# RaspberryShield.net
KiCad netlist of a schematic drawn in EAGLE
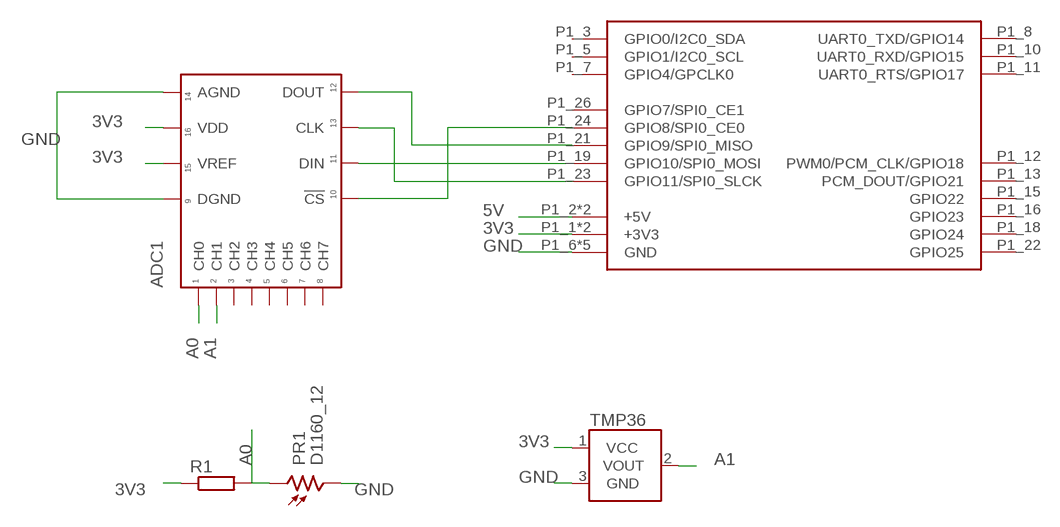
[diagram p0: schematic, sheet 1]

(export (version "E")
  (design (tool "Eeschema 10.0.6"))
  (components
    (comp (ref "ADC1")
      (value "21298EDIP")
      (footprint "eagle-import:DIP16")
      (libsource (lib "eagle-import") (part "21298EDIP"))
    )
    (comp (ref "PR1")
      (value "D1160_12")
      (footprint "eagle-import:D11XX")
      (libsource (lib "eagle-import") (part "D1160_12"))
    )
    (comp (ref "R1")
      (value "R-EU_0207/7")
      (footprint "eagle-import:0207_7")
      (libsource (lib "eagle-import") (part "R-EU_0207/7"))
    )
    (comp (ref "TMP36")
      (value "TMP36GT9")
      (footprint "eagle-import:TO-92")
      (libsource (lib "eagle-import") (part "TMP36GT9"))
    )
    (comp (ref "U$1")
      (value "RPI-B-V1SHIELD")
      (footprint "eagle-import:RPI-B-V1-SHIELD")
      (libsource (lib "eagle-import") (part "RPI-B-V1SHIELD"))
    )
  )
  (nets
    (net (code "1") (name "/3V3") (class "Default")
      (node (ref "ADC1") (pin "P$15") (pinfunction "VREF_P$15") (pintype "bidirectional"))
      (node (ref "ADC1") (pin "P$16") (pinfunction "VDD_P$16") (pintype "bidirectional"))
      (node (ref "R1") (pin "1") (pinfunction "1_1") (pintype "passive"))
      (node (ref "TMP36") (pin "1") (pinfunction "VCC_1") (pintype "bidirectional"))
      (node (ref "U$1") (pin "P1_1") (pinfunction "+3V3_P1_1") (pintype "power_in"))
      (node (ref "U$1") (pin "P1_17") (pinfunction "+3V3_P1_17") (pintype "power_in"))
    )
    (net (code "2") (name "/5V") (class "Default")
      (node (ref "U$1") (pin "P1_2") (pinfunction "+5V_P1_2") (pintype "power_in"))
      (node (ref "U$1") (pin "P1_4") (pinfunction "+5V_P1_4") (pintype "power_in"))
    )
    (net (code "3") (name "/A0") (class "Default")
      (node (ref "ADC1") (pin "P$1") (pinfunction "CH0_P$1") (pintype "bidirectional"))
      (node (ref "PR1") (pin "1") (pinfunction "1_1") (pintype "passive"))
      (node (ref "R1") (pin "2") (pinfunction "2_2") (pintype "passive"))
    )
    (net (code "4") (name "/A1") (class "Default")
      (node (ref "ADC1") (pin "P$2") (pinfunction "CH1_P$2") (pintype "bidirectional"))
      (node (ref "TMP36") (pin "2") (pinfunction "VOUT_2") (pintype "bidirectional"))
    )
    (net (code "5") (name "/GND") (class "Default")
      (node (ref "ADC1") (pin "P$14") (pinfunction "AGND_P$14") (pintype "bidirectional"))
      (node (ref "ADC1") (pin "P$9") (pinfunction "DGND_P$9") (pintype "bidirectional"))
      (node (ref "PR1") (pin "2") (pinfunction "2_2") (pintype "passive"))
      (node (ref "TMP36") (pin "3") (pinfunction "GND_3") (pintype "bidirectional"))
      (node (ref "U$1") (pin "P1_14") (pinfunction "GND_P1_14") (pintype "power_in"))
      (node (ref "U$1") (pin "P1_20") (pinfunction "GND_P1_20") (pintype "power_in"))
      (node (ref "U$1") (pin "P1_25") (pinfunction "GND_P1_25") (pintype "power_in"))
      (node (ref "U$1") (pin "P1_6") (pinfunction "GND_P1_6") (pintype "power_in"))
      (node (ref "U$1") (pin "P1_9") (pinfunction "GND_P1_9") (pintype "power_in"))
    )
    (net (code "6") (name "Net-(ADC1-CLK)") (class "Default")
      (node (ref "ADC1") (pin "P$13") (pinfunction "CLK_P$13") (pintype "bidirectional"))
      (node (ref "U$1") (pin "P1_23") (pinfunction "GPIO11/SPI0_SLCK_P1_23") (pintype "bidirectional"))
    )
    (net (code "7") (name "Net-(ADC1-DIN)") (class "Default")
      (node (ref "ADC1") (pin "P$11") (pinfunction "DIN_P$11") (pintype "bidirectional"))
      (node (ref "U$1") (pin "P1_19") (pinfunction "GPIO10/SPI0_MOSI_P1_19") (pintype "bidirectional"))
    )
    (net (code "8") (name "Net-(ADC1-DOUT)") (class "Default")
      (node (ref "ADC1") (pin "P$12") (pinfunction "DOUT_P$12") (pintype "bidirectional"))
      (node (ref "U$1") (pin "P1_21") (pinfunction "GPIO9/SPI0_MISO_P1_21") (pintype "bidirectional"))
    )
    (net (code "9") (name "Net-(ADC1-~{CS})") (class "Default")
      (node (ref "ADC1") (pin "P$10") (pinfunction "~{CS}_P$10") (pintype "bidirectional"))
      (node (ref "U$1") (pin "P1_24") (pinfunction "GPIO8/SPI0_CE0_P1_24") (pintype "bidirectional"))
    )
    (net (code "10") (name "unconnected-(ADC1-CH2-PadP$3)") (class "Default")
      (node (ref "ADC1") (pin "P$3") (pinfunction "CH2_P$3") (pintype "bidirectional"))
    )
    (net (code "11") (name "unconnected-(ADC1-CH3-PadP$4)") (class "Default")
      (node (ref "ADC1") (pin "P$4") (pinfunction "CH3_P$4") (pintype "bidirectional"))
    )
    (net (code "12") (name "unconnected-(ADC1-CH4-PadP$5)") (class "Default")
      (node (ref "ADC1") (pin "P$5") (pinfunction "CH4_P$5") (pintype "bidirectional"))
    )
    (net (code "13") (name "unconnected-(ADC1-CH5-PadP$6)") (class "Default")
      (node (ref "ADC1") (pin "P$6") (pinfunction "CH5_P$6") (pintype "bidirectional"))
    )
    (net (code "14") (name "unconnected-(ADC1-CH6-PadP$7)") (class "Default")
      (node (ref "ADC1") (pin "P$7") (pinfunction "CH6_P$7") (pintype "bidirectional"))
    )
    (net (code "15") (name "unconnected-(ADC1-CH7-PadP$8)") (class "Default")
      (node (ref "ADC1") (pin "P$8") (pinfunction "CH7_P$8") (pintype "bidirectional"))
    )
    (net (code "16") (name "unconnected-(U$1-GPIO0{slash}I2C0_SDA-PadP1_3)") (class "Default")
      (node (ref "U$1") (pin "P1_3") (pinfunction "GPIO0/I2C0_SDA_P1_3") (pintype "bidirectional"))
    )
    (net (code "17") (name "unconnected-(U$1-GPIO1{slash}I2C0_SCL-PadP1_5)") (class "Default")
      (node (ref "U$1") (pin "P1_5") (pinfunction "GPIO1/I2C0_SCL_P1_5") (pintype "bidirectional"))
    )
    (net (code "18") (name "unconnected-(U$1-GPIO4{slash}GPCLK0-PadP1_7)") (class "Default")
      (node (ref "U$1") (pin "P1_7") (pinfunction "GPIO4/GPCLK0_P1_7") (pintype "bidirectional"))
    )
    (net (code "19") (name "unconnected-(U$1-GPIO7{slash}SPI0_CE1-PadP1_26)") (class "Default")
      (node (ref "U$1") (pin "P1_26") (pinfunction "GPIO7/SPI0_CE1_P1_26") (pintype "bidirectional"))
    )
    (net (code "20") (name "unconnected-(U$1-GPIO22-PadP1_15)") (class "Default")
      (node (ref "U$1") (pin "P1_15") (pinfunction "GPIO22_P1_15") (pintype "bidirectional"))
    )
    (net (code "21") (name "unconnected-(U$1-GPIO23-PadP1_16)") (class "Default")
      (node (ref "U$1") (pin "P1_16") (pinfunction "GPIO23_P1_16") (pintype "bidirectional"))
    )
    (net (code "22") (name "unconnected-(U$1-GPIO24-PadP1_18)") (class "Default")
      (node (ref "U$1") (pin "P1_18") (pinfunction "GPIO24_P1_18") (pintype "bidirectional"))
    )
    (net (code "23") (name "unconnected-(U$1-GPIO25-PadP1_22)") (class "Default")
      (node (ref "U$1") (pin "P1_22") (pinfunction "GPIO25_P1_22") (pintype "bidirectional"))
    )
    (net (code "24") (name "unconnected-(U$1-PCM_DOUT{slash}GPIO21-PadP1_13)") (class "Default")
      (node (ref "U$1") (pin "P1_13") (pinfunction "PCM_DOUT/GPIO21_P1_13") (pintype "bidirectional"))
    )
    (net (code "25") (name "unconnected-(U$1-PWM0{slash}PCM_CLK{slash}GPIO18-PadP1_12)") (class "Default")
      (node (ref "U$1") (pin "P1_12") (pinfunction "PWM0/PCM_CLK/GPIO18_P1_12") (pintype "bidirectional"))
    )
    (net (code "26") (name "unconnected-(U$1-UART0_RTS{slash}GPIO17-PadP1_11)") (class "Default")
      (node (ref "U$1") (pin "P1_11") (pinfunction "UART0_RTS/GPIO17_P1_11") (pintype "bidirectional"))
    )
    (net (code "27") (name "unconnected-(U$1-UART0_RXD{slash}GPIO15-PadP1_10)") (class "Default")
      (node (ref "U$1") (pin "P1_10") (pinfunction "UART0_RXD/GPIO15_P1_10") (pintype "bidirectional"))
    )
    (net (code "28") (name "unconnected-(U$1-UART0_TXD{slash}GPIO14-PadP1_8)") (class "Default")
      (node (ref "U$1") (pin "P1_8") (pinfunction "UART0_TXD/GPIO14_P1_8") (pintype "bidirectional"))
    )
  )
)
